# Lambda-Sensor-Driver.net
KiCad netlist of a schematic drawn in Altium Designer
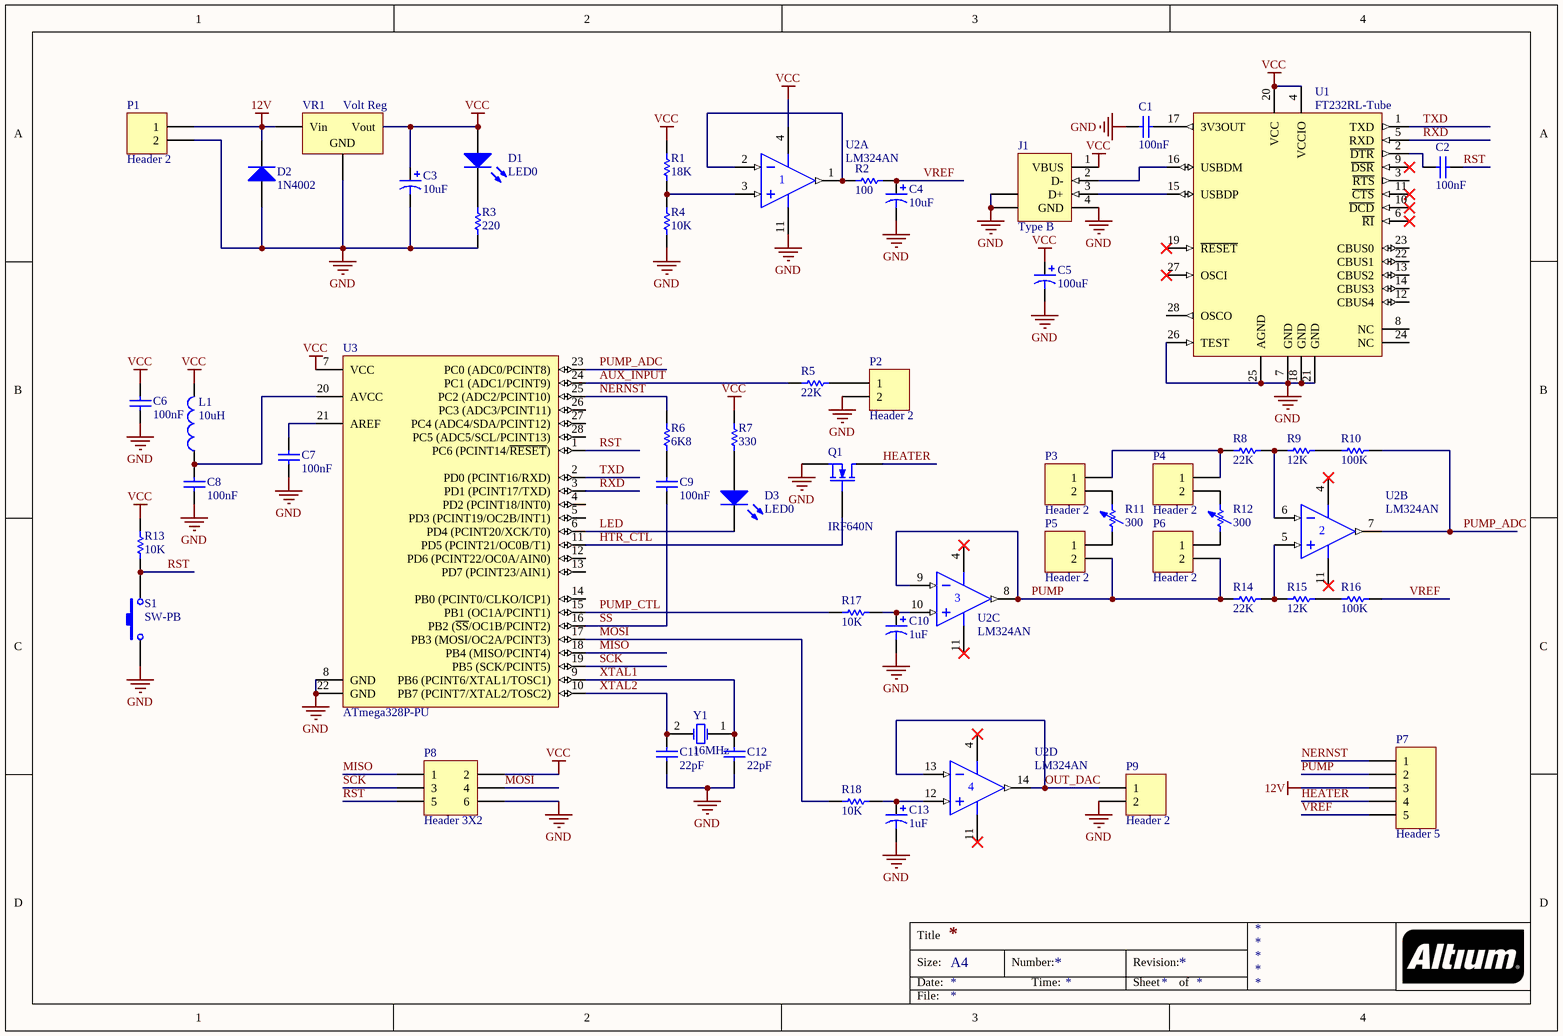
[diagram p0: Lambda-Sensor-Driver.SchDoc]

(export (version "E")
  (design (tool "Eeschema 10.0.6"))
  (components
    (comp (ref "C1")
      (value "100nF")
      (footprint "toko-Embedded:C0805")
      (description "Capacitor")
      (fields (field (name "PUBLISHER") "Altium Limited"))
      (libsource (lib "Miscellaneous Devices") (part "Cap"))
    )
    (comp (ref "C2")
      (value "100nF")
      (footprint "toko-Embedded:C0805")
      (description "Capacitor")
      (fields (field (name "PUBLISHER") "Altium Limited"))
      (libsource (lib "Miscellaneous Devices") (part "Cap"))
    )
    (comp (ref "C3")
      (value "10uF")
      (footprint "toko-Embedded:E2,5-5")
      (description "Polarized Capacitor (Radial)")
      (fields (field (name "PUBLISHER") "Altium Limited"))
      (libsource (lib "Miscellaneous Devices") (part "Cap Pol1"))
    )
    (comp (ref "C4")
      (value "10uF")
      (footprint "toko-Embedded:E2,5-5")
      (description "Polarized Capacitor (Radial)")
      (fields (field (name "PUBLISHER") "Altium Limited"))
      (libsource (lib "Miscellaneous Devices") (part "Cap Pol1"))
    )
    (comp (ref "C5")
      (value "100uF")
      (footprint "toko-Embedded:E2,5-5")
      (description "Polarized Capacitor (Radial)")
      (fields (field (name "PUBLISHER") "Altium Limited"))
      (libsource (lib "Miscellaneous Devices") (part "Cap Pol1"))
    )
    (comp (ref "C6")
      (value "100nF")
      (footprint "toko-Embedded:C025-024X044")
      (description "Capacitor")
      (fields (field (name "PUBLISHER") "Altium Limited"))
      (libsource (lib "Miscellaneous Devices") (part "Cap"))
    )
    (comp (ref "C7")
      (value "100nF")
      (footprint "toko-Embedded:C025-024X044")
      (description "Capacitor")
      (fields (field (name "PUBLISHER") "Altium Limited"))
      (libsource (lib "Miscellaneous Devices") (part "Cap"))
    )
    (comp (ref "C8")
      (value "100nF")
      (footprint "toko-Embedded:C025-024X044")
      (description "Capacitor")
      (fields (field (name "PUBLISHER") "Altium Limited"))
      (libsource (lib "Miscellaneous Devices") (part "Cap"))
    )
    (comp (ref "C9")
      (value "100nF")
      (footprint "toko-Embedded:C025-024X044")
      (description "Capacitor")
      (fields (field (name "PUBLISHER") "Altium Limited"))
      (libsource (lib "Miscellaneous Devices") (part "Cap"))
    )
    (comp (ref "C10")
      (value "1uF")
      (footprint "toko-Embedded:E2,5-5")
      (description "Polarized Capacitor (Radial)")
      (fields (field (name "PUBLISHER") "Altium Limited"))
      (libsource (lib "Miscellaneous Devices") (part "Cap Pol1"))
    )
    (comp (ref "C11")
      (value "22pF")
      (footprint "toko-Embedded:C025-024X044")
      (description "Capacitor")
      (fields (field (name "PUBLISHER") "Altium Limited"))
      (libsource (lib "Miscellaneous Devices") (part "Cap"))
    )
    (comp (ref "C12")
      (value "22pF")
      (footprint "toko-Embedded:C025-024X044")
      (description "Capacitor")
      (fields (field (name "PUBLISHER") "Altium Limited"))
      (libsource (lib "Miscellaneous Devices") (part "Cap"))
    )
    (comp (ref "C13")
      (value "1uF")
      (footprint "toko-Embedded:E2,5-5")
      (description "Polarized Capacitor (Radial)")
      (fields (field (name "PUBLISHER") "Altium Limited"))
      (libsource (lib "Miscellaneous Devices") (part "Cap Pol1"))
    )
    (comp (ref "D1")
      (value "LED0")
      (footprint "toko-Embedded:LED3MM")
      (description "Typical INFRARED GaAs LED")
      (fields (field (name "PUBLISHER") "Altium Limited"))
      (libsource (lib "Miscellaneous Devices") (part "LED0"))
    )
    (comp (ref "D2")
      (value "1N4002")
      (footprint "toko-Embedded:DO41-10")
      (description "Default Diode")
      (fields (field (name "PUBLISHER") "Altium Limited"))
      (libsource (lib "Miscellaneous Devices") (part "Diode"))
    )
    (comp (ref "D3")
      (value "LED0")
      (footprint "toko-Embedded:LED3MM")
      (description "Typical INFRARED GaAs LED")
      (fields (field (name "PUBLISHER") "Altium Limited"))
      (libsource (lib "Miscellaneous Devices") (part "LED0"))
    )
    (comp (ref "J1") (value "Type B") (footprint "USB-B-PTH") (libsource (lib "toko-Embedded") (part "USB")))
    (comp (ref "L1")
      (value "10uH")
      (footprint "toko-Embedded:0207/10")
      (description "Inductor")
      (fields (field (name "PUBLISHER") "Altium Limited"))
      (libsource (lib "Miscellaneous Devices") (part "Inductor"))
    )
    (comp (ref "P1")
      (value "Header 2")
      (footprint "toko-Embedded:W237-132")
      (description "Header, 2-Pin")
      (fields (field (name "PUBLISHER") "Altium Limited"))
      (libsource (lib "Miscellaneous Connectors") (part "Header 2"))
    )
    (comp (ref "P2")
      (value "Header 2")
      (footprint "toko-Embedded:W237-132")
      (description "Header, 2-Pin")
      (fields (field (name "PUBLISHER") "Altium Limited"))
      (libsource (lib "") (part "Header 2_1"))
    )
    (comp (ref "P3")
      (value "Header 2")
      (footprint "Miscellaneous Connectors:HDR1X2")
      (description "Header, 2-Pin")
      (fields (field (name "PUBLISHER") "Altium Limited"))
      (libsource (lib "Miscellaneous Connectors") (part "Header 2"))
    )
    (comp (ref "P4")
      (value "Header 2")
      (footprint "Miscellaneous Connectors:HDR1X2")
      (description "Header, 2-Pin")
      (fields (field (name "PUBLISHER") "Altium Limited"))
      (libsource (lib "Miscellaneous Connectors") (part "Header 2"))
    )
    (comp (ref "P5")
      (value "Header 2")
      (footprint "Miscellaneous Connectors:HDR1X2")
      (description "Header, 2-Pin")
      (fields (field (name "PUBLISHER") "Altium Limited"))
      (libsource (lib "Miscellaneous Connectors") (part "Header 2"))
    )
    (comp (ref "P6")
      (value "Header 2")
      (footprint "Miscellaneous Connectors:HDR1X2")
      (description "Header, 2-Pin")
      (fields (field (name "PUBLISHER") "Altium Limited"))
      (libsource (lib "Miscellaneous Connectors") (part "Header 2"))
    )
    (comp (ref "P7")
      (value "Header 5")
      (footprint "toko-Embedded:W237-6P")
      (description "Header, 5-Pin")
      (fields (field (name "PUBLISHER") "Altium Limited"))
      (libsource (lib "Miscellaneous Connectors") (part "Header 5"))
    )
    (comp (ref "P8")
      (value "Header 3X2")
      (footprint "HDR2X3")
      (description "Header, 3-Pin, Dual row")
      (fields (field (name "PUBLISHER") "Altium Limited"))
      (libsource (lib "Miscellaneous Connectors") (part "Header 3X2"))
    )
    (comp (ref "P9")
      (value "Header 2")
      (footprint "toko-Embedded:W237-132")
      (description "Header, 2-Pin")
      (fields (field (name "PUBLISHER") "Altium Limited"))
      (libsource (lib "") (part "Header 2_1"))
    )
    (comp (ref "Q1")
      (value "IRF640N")
      (footprint "toko-Embedded:TO220V")
      (description "N-Channel MOSFET")
      (fields (field (name "PUBLISHER") "Altium Limited"))
      (libsource (lib "Miscellaneous Devices") (part "MOSFET-N"))
    )
    (comp (ref "R1")
      (value "18K")
      (footprint "toko-Embedded:0207/10")
      (description "Resistor")
      (fields (field (name "PUBLISHER") "Altium Limited"))
      (libsource (lib "Miscellaneous Devices") (part "Res1"))
    )
    (comp (ref "R2")
      (value "100")
      (footprint "toko-Embedded:0207/10")
      (description "Resistor")
      (fields (field (name "PUBLISHER") "Altium Limited"))
      (libsource (lib "Miscellaneous Devices") (part "Res1"))
    )
    (comp (ref "R3")
      (value "220")
      (footprint "toko-Embedded:0207/10")
      (description "Resistor")
      (fields (field (name "PUBLISHER") "Altium Limited"))
      (libsource (lib "Miscellaneous Devices") (part "Res1"))
    )
    (comp (ref "R4")
      (value "10K")
      (footprint "toko-Embedded:0207/10")
      (description "Resistor")
      (fields (field (name "PUBLISHER") "Altium Limited"))
      (libsource (lib "Miscellaneous Devices") (part "Res1"))
    )
    (comp (ref "R5")
      (value "22K")
      (footprint "toko-Embedded:0207/10")
      (description "Resistor")
      (fields (field (name "PUBLISHER") "Altium Limited"))
      (libsource (lib "Miscellaneous Devices") (part "Res1"))
    )
    (comp (ref "R6")
      (value "6K8")
      (footprint "toko-Embedded:0207/10")
      (description "Resistor")
      (fields (field (name "PUBLISHER") "Altium Limited"))
      (libsource (lib "Miscellaneous Devices") (part "Res1"))
    )
    (comp (ref "R7")
      (value "330")
      (footprint "toko-Embedded:0207/10")
      (description "Resistor")
      (fields (field (name "PUBLISHER") "Altium Limited"))
      (libsource (lib "Miscellaneous Devices") (part "Res1"))
    )
    (comp (ref "R8")
      (value "22K")
      (footprint "toko-Embedded:0207/10")
      (description "Resistor")
      (fields (field (name "PUBLISHER") "Altium Limited"))
      (libsource (lib "Miscellaneous Devices") (part "Res1"))
    )
    (comp (ref "R9")
      (value "12K")
      (footprint "toko-Embedded:0207/10")
      (description "Resistor")
      (fields (field (name "PUBLISHER") "Altium Limited"))
      (libsource (lib "Miscellaneous Devices") (part "Res1"))
    )
    (comp (ref "R10")
      (value "100K")
      (footprint "toko-Embedded:0207/10")
      (description "Resistor")
      (fields (field (name "PUBLISHER") "Altium Limited"))
      (libsource (lib "Miscellaneous Devices") (part "Res1"))
    )
    (comp (ref "R11")
      (value "300")
      (footprint "toko-Embedded:CA6V")
      (description "Variable Resistor")
      (fields (field (name "PUBLISHER") "Altium Limited"))
      (libsource (lib "Miscellaneous Devices") (part "Res Adj1"))
    )
    (comp (ref "R12")
      (value "300")
      (footprint "toko-Embedded:CA6V")
      (description "Variable Resistor")
      (fields (field (name "PUBLISHER") "Altium Limited"))
      (libsource (lib "Miscellaneous Devices") (part "Res Adj1"))
    )
    (comp (ref "R13")
      (value "10K")
      (footprint "toko-Embedded:0207/10")
      (description "Resistor")
      (fields (field (name "PUBLISHER") "Altium Limited"))
      (libsource (lib "Miscellaneous Devices") (part "Res1"))
    )
    (comp (ref "R14")
      (value "22K")
      (footprint "toko-Embedded:0207/10")
      (description "Resistor")
      (fields (field (name "PUBLISHER") "Altium Limited"))
      (libsource (lib "Miscellaneous Devices") (part "Res1"))
    )
    (comp (ref "R15")
      (value "12K")
      (footprint "toko-Embedded:0207/10")
      (description "Resistor")
      (fields (field (name "PUBLISHER") "Altium Limited"))
      (libsource (lib "Miscellaneous Devices") (part "Res1"))
    )
    (comp (ref "R16")
      (value "100K")
      (footprint "toko-Embedded:0207/10")
      (description "Resistor")
      (fields (field (name "PUBLISHER") "Altium Limited"))
      (libsource (lib "Miscellaneous Devices") (part "Res1"))
    )
    (comp (ref "R17")
      (value "10K")
      (footprint "toko-Embedded:0207/10")
      (description "Resistor")
      (fields (field (name "PUBLISHER") "Altium Limited"))
      (libsource (lib "Miscellaneous Devices") (part "Res1"))
    )
    (comp (ref "R18")
      (value "10K")
      (footprint "toko-Embedded:0207/10")
      (description "Resistor")
      (fields (field (name "PUBLISHER") "Altium Limited"))
      (libsource (lib "Miscellaneous Devices") (part "Res1"))
    )
    (comp (ref "S1")
      (value "SW-PB")
      (footprint "toko-Embedded:TACTILE-PTH")
      (description "Switch")
      (fields (field (name "PUBLISHER") "Altium Limited"))
      (libsource (lib "Miscellaneous Devices") (part "SW-PB"))
    )
    (comp (ref "U1")
      (value "FT232RL-Tube")
      (footprint "SSOP-28_N")
      (description "USB UART Asynchronous Serial Data Transfer Chip, SSOP-28, Tube")
      (fields (field (name "PUBLISHER") "Altium Limited"))
      (libsource (lib "FTDI Communication UART") (part "FT232RL-Tube"))
    )
    (comp (ref "U2")
      (value "LM324AN")
      (footprint "646-06")
      (description "Quad Low-Power Operational Amplifier")
      (fields (field (name "PUBLISHER") "Altium Limited"))
      (libsource (lib "Motorola Amplifier Operational Amplifier") (part "LM324AN"))
    )
    (comp (ref "U3")
      (value "ATmega328P-PU")
      (footprint "28P3")
      (fields (field (name "PUBLISHER") "Altium Limited"))
      (libsource (lib "Atmel Microcontroller 8-Bit megaAVR") (part "ATmega328P-PU"))
    )
    (comp (ref "VR1")
      (value "Volt Reg")
      (footprint "toko-Embedded:TO220V")
      (description "Voltage Regulator")
      (fields (field (name "PUBLISHER") "Altium Limited"))
      (libsource (lib "Miscellaneous Devices") (part "Volt Reg"))
    )
    (comp (ref "Y1")
      (value "16MHz")
      (footprint "toko-Embedded:HC49US")
      (description "Crystal Oscillator")
      (fields (field (name "PUBLISHER") "Altium Limited"))
      (libsource (lib "Miscellaneous Devices") (part "XTAL"))
    )
  )
  (nets
    (net (code "1") (name "/AUX_INPUT") (class "Default")
      (node (ref "R5") (pin "2") (pinfunction "2_2") (pintype "passive"))
      (node (ref "U3") (pin "24") (pinfunction "PC1_(ADC1/PCINT9)_24") (pintype "bidirectional"))
    )
    (net (code "2") (name "/HEATER") (class "Default")
      (node (ref "P7") (pin "4") (pinfunction "4_4") (pintype "passive"))
      (node (ref "Q1") (pin "2") (pinfunction "D_2") (pintype "passive"))
    )
    (net (code "3") (name "/HTR_CTL") (class "Default")
      (node (ref "Q1") (pin "1") (pinfunction "G_1") (pintype "passive"))
      (node (ref "U3") (pin "11") (pinfunction "PD5_(PCINT21/OC0B/T1)_11") (pintype "bidirectional"))
    )
    (net (code "4") (name "/LED") (class "Default")
      (node (ref "D3") (pin "2") (pinfunction "K_2") (pintype "passive"))
      (node (ref "U3") (pin "6") (pinfunction "PD4_(PCINT20/XCK/T0)_6") (pintype "bidirectional"))
    )
    (net (code "5") (name "/MISO") (class "Default")
      (node (ref "P8") (pin "1") (pinfunction "1_1") (pintype "passive"))
      (node (ref "U3") (pin "18") (pinfunction "PB4_(MISO/PCINT4)_18") (pintype "bidirectional"))
    )
    (net (code "6") (name "/MOSI") (class "Default")
      (node (ref "P8") (pin "4") (pinfunction "4_4") (pintype "passive"))
      (node (ref "R18") (pin "1") (pinfunction "1_1") (pintype "passive"))
      (node (ref "U3") (pin "17") (pinfunction "PB3_(MOSI/OC2A/PCINT3)_17") (pintype "bidirectional"))
    )
    (net (code "7") (name "/NERNST") (class "Default")
      (node (ref "P7") (pin "1") (pinfunction "1_1") (pintype "passive"))
      (node (ref "R6") (pin "1") (pinfunction "1_1") (pintype "passive"))
      (node (ref "U3") (pin "25") (pinfunction "PC2_(ADC2/PCINT10)_25") (pintype "bidirectional"))
    )
    (net (code "8") (name "/OUT_DAC") (class "Default")
      (node (ref "P9") (pin "1") (pinfunction "1_1") (pintype "passive"))
      (node (ref "U2") (pin "13") (pinfunction "IN-_13") (pintype "input"))
      (node (ref "U2") (pin "14") (pinfunction "OUT_14") (pintype "output"))
    )
    (net (code "9") (name "/PUMP") (class "Default")
      (node (ref "P5") (pin "2") (pinfunction "2_2") (pintype "passive"))
      (node (ref "P6") (pin "2") (pinfunction "2_2") (pintype "passive"))
      (node (ref "P7") (pin "2") (pinfunction "2_2") (pintype "passive"))
      (node (ref "R14") (pin "2") (pinfunction "2_2") (pintype "passive"))
      (node (ref "U2") (pin "8") (pinfunction "OUT_8") (pintype "output"))
      (node (ref "U2") (pin "9") (pinfunction "IN-_9") (pintype "input"))
    )
    (net (code "10") (name "/PUMP_ADC") (class "Default")
      (node (ref "R10") (pin "1") (pinfunction "1_1") (pintype "passive"))
      (node (ref "U2") (pin "7") (pinfunction "OUT_7") (pintype "output"))
      (node (ref "U3") (pin "23") (pinfunction "PC0_(ADC0/PCINT8)_23") (pintype "bidirectional"))
    )
    (net (code "11") (name "/PUMP_CTL") (class "Default")
      (node (ref "R17") (pin "1") (pinfunction "1_1") (pintype "passive"))
      (node (ref "U3") (pin "15") (pinfunction "PB1_(OC1A/PCINT1)_15") (pintype "bidirectional"))
    )
    (net (code "12") (name "/RST") (class "Default")
      (node (ref "C2") (pin "1") (pinfunction "1_1") (pintype "passive"))
      (node (ref "P8") (pin "5") (pinfunction "5_5") (pintype "passive"))
      (node (ref "R13") (pin "2") (pinfunction "2_2") (pintype "passive"))
      (node (ref "S1") (pin "2") (pinfunction "2_2") (pintype "passive"))
      (node (ref "U3") (pin "1") (pinfunction "PC6_(PCINT14/~{RESET})_1") (pintype "bidirectional"))
    )
    (net (code "13") (name "/RXD") (class "Default")
      (node (ref "U1") (pin "5") (pinfunction "RXD_5") (pintype "input"))
      (node (ref "U3") (pin "3") (pinfunction "PD1_(PCINT17/TXD)_3") (pintype "bidirectional"))
    )
    (net (code "14") (name "/SCK") (class "Default")
      (node (ref "P8") (pin "3") (pinfunction "3_3") (pintype "passive"))
      (node (ref "U3") (pin "19") (pinfunction "PB5_(SCK/PCINT5)_19") (pintype "bidirectional"))
    )
    (net (code "15") (name "/SS") (class "Default")
      (node (ref "C9") (pin "1") (pinfunction "1_1") (pintype "passive"))
      (node (ref "U3") (pin "16") (pinfunction "PB2_(~{SS}/OC1B/PCINT2)_16") (pintype "bidirectional"))
    )
    (net (code "16") (name "/TXD") (class "Default")
      (node (ref "U1") (pin "1") (pinfunction "TXD_1") (pintype "output"))
      (node (ref "U3") (pin "2") (pinfunction "PD0_(PCINT16/RXD)_2") (pintype "bidirectional"))
    )
    (net (code "17") (name "/VREF") (class "Default")
      (node (ref "C4") (pin "1") (pinfunction "1_1") (pintype "passive"))
      (node (ref "P7") (pin "5") (pinfunction "5_5") (pintype "passive"))
      (node (ref "R16") (pin "1") (pinfunction "1_1") (pintype "passive"))
      (node (ref "R2") (pin "1") (pinfunction "1_1") (pintype "passive"))
    )
    (net (code "18") (name "/XTAL1") (class "Default")
      (node (ref "C12") (pin "2") (pinfunction "2_2") (pintype "passive"))
      (node (ref "U3") (pin "9") (pinfunction "PB6_(PCINT6/XTAL1/TOSC1)_9") (pintype "bidirectional"))
      (node (ref "Y1") (pin "1") (pinfunction "OSC1_1") (pintype "passive"))
    )
    (net (code "19") (name "/XTAL2") (class "Default")
      (node (ref "C11") (pin "2") (pinfunction "2_2") (pintype "passive"))
      (node (ref "U3") (pin "10") (pinfunction "PB7_(PCINT7/XTAL2/TOSC2)_10") (pintype "bidirectional"))
      (node (ref "Y1") (pin "2") (pinfunction "OSC2_2") (pintype "passive"))
    )
    (net (code "20") (name "12V") (class "Default")
      (node (ref "D2") (pin "2") (pinfunction "K_2") (pintype "passive"))
      (node (ref "P1") (pin "1") (pinfunction "1_1") (pintype "passive"))
      (node (ref "P7") (pin "3") (pinfunction "3_3") (pintype "passive"))
      (node (ref "VR1") (pin "1") (pinfunction "Vin_1") (pintype "passive"))
    )
    (net (code "21") (name "GND") (class "Default")
      (node (ref "C1") (pin "2") (pinfunction "2_2") (pintype "passive"))
      (node (ref "C10") (pin "2") (pinfunction "2_2") (pintype "passive"))
      (node (ref "C11") (pin "1") (pinfunction "1_1") (pintype "passive"))
      (node (ref "C12") (pin "1") (pinfunction "1_1") (pintype "passive"))
      (node (ref "C13") (pin "2") (pinfunction "2_2") (pintype "passive"))
      (node (ref "C3") (pin "2") (pinfunction "2_2") (pintype "passive"))
      (node (ref "C4") (pin "2") (pinfunction "2_2") (pintype "passive"))
      (node (ref "C5") (pin "2") (pinfunction "2_2") (pintype "passive"))
      (node (ref "C6") (pin "1") (pinfunction "1_1") (pintype "passive"))
      (node (ref "C7") (pin "1") (pinfunction "1_1") (pintype "passive"))
      (node (ref "C8") (pin "1") (pinfunction "1_1") (pintype "passive"))
      (node (ref "D2") (pin "1") (pinfunction "A_1") (pintype "passive"))
      (node (ref "J1") (pin "4") (pinfunction "GND_4") (pintype "power_in"))
      (node (ref "J1") (pin "5") (pinfunction "SHLD_5") (pintype "passive"))
      (node (ref "J1") (pin "6") (pinfunction "SHLD_6") (pintype "passive"))
      (node (ref "P1") (pin "2") (pinfunction "2_2") (pintype "passive"))
      (node (ref "P2") (pin "2") (pinfunction "2_2") (pintype "passive"))
      (node (ref "P8") (pin "6") (pinfunction "6_6") (pintype "passive"))
      (node (ref "P9") (pin "2") (pinfunction "2_2") (pintype "passive"))
      (node (ref "Q1") (pin "3") (pinfunction "S_3") (pintype "passive"))
      (node (ref "R3") (pin "1") (pinfunction "1_1") (pintype "passive"))
      (node (ref "R4") (pin "1") (pinfunction "1_1") (pintype "passive"))
      (node (ref "S1") (pin "1") (pinfunction "1_1") (pintype "passive"))
      (node (ref "U1") (pin "18") (pinfunction "GND_18") (pintype "power_in"))
      (node (ref "U1") (pin "21") (pinfunction "GND_21") (pintype "power_in"))
      (node (ref "U1") (pin "25") (pinfunction "AGND_25") (pintype "power_in"))
      (node (ref "U1") (pin "26") (pinfunction "TEST_26") (pintype "input"))
      (node (ref "U1") (pin "7") (pinfunction "GND_7") (pintype "power_in"))
      (node (ref "U2") (pin "11") (pinfunction "V-_11") (pintype "power_in"))
      (node (ref "U3") (pin "22") (pinfunction "GND_22") (pintype "power_in"))
      (node (ref "U3") (pin "8") (pinfunction "GND_8") (pintype "power_in"))
      (node (ref "VR1") (pin "2") (pinfunction "GND_2") (pintype "passive"))
    )
    (net (code "22") (name "Net-(C9-Pad2)") (class "Default")
      (node (ref "C9") (pin "2") (pinfunction "2_2") (pintype "passive"))
      (node (ref "R6") (pin "2") (pinfunction "2_2") (pintype "passive"))
    )
    (net (code "23") (name "Net-(D1-K)") (class "Default")
      (node (ref "D1") (pin "2") (pinfunction "K_2") (pintype "passive"))
      (node (ref "R3") (pin "2") (pinfunction "2_2") (pintype "passive"))
    )
    (net (code "24") (name "Net-(D3-A)") (class "Default")
      (node (ref "D3") (pin "1") (pinfunction "A_1") (pintype "passive"))
      (node (ref "R7") (pin "2") (pinfunction "2_2") (pintype "passive"))
    )
    (net (code "25") (name "Net-(J1-D+)") (class "Default")
      (node (ref "J1") (pin "3") (pinfunction "D+_3") (pintype "input"))
      (node (ref "U1") (pin "15") (pinfunction "USBDP_15") (pintype "bidirectional"))
    )
    (net (code "26") (name "Net-(J1-D-)") (class "Default")
      (node (ref "J1") (pin "2") (pinfunction "D-_2") (pintype "input"))
      (node (ref "U1") (pin "16") (pinfunction "USBDM_16") (pintype "bidirectional"))
    )
    (net (code "27") (name "Net-(P2-Pad1)") (class "Default")
      (node (ref "P2") (pin "1") (pinfunction "1_1") (pintype "passive"))
      (node (ref "R5") (pin "1") (pinfunction "1_1") (pintype "passive"))
    )
    (net (code "28") (name "Net-(P3-Pad1)") (class "Default")
      (node (ref "P3") (pin "1") (pinfunction "1_1") (pintype "passive"))
      (node (ref "P4") (pin "1") (pinfunction "1_1") (pintype "passive"))
      (node (ref "R8") (pin "2") (pinfunction "2_2") (pintype "passive"))
    )
    (net (code "29") (name "Net-(P3-Pad2)") (class "Default")
      (node (ref "P3") (pin "2") (pinfunction "2_2") (pintype "passive"))
      (node (ref "R11") (pin "2") (pinfunction "2_2") (pintype "passive"))
    )
    (net (code "30") (name "Net-(P4-Pad2)") (class "Default")
      (node (ref "P4") (pin "2") (pinfunction "2_2") (pintype "passive"))
      (node (ref "R12") (pin "2") (pinfunction "2_2") (pintype "passive"))
    )
    (net (code "31") (name "Net-(P5-Pad1)") (class "Default")
      (node (ref "P5") (pin "1") (pinfunction "1_1") (pintype "passive"))
      (node (ref "R11") (pin "1") (pinfunction "1_1") (pintype "passive"))
    )
    (net (code "32") (name "Net-(P6-Pad1)") (class "Default")
      (node (ref "P6") (pin "1") (pinfunction "1_1") (pintype "passive"))
      (node (ref "R12") (pin "1") (pinfunction "1_1") (pintype "passive"))
    )
    (net (code "33") (name "Net-(R10-Pad2)") (class "Default")
      (node (ref "R10") (pin "2") (pinfunction "2_2") (pintype "passive"))
      (node (ref "R9") (pin "1") (pinfunction "1_1") (pintype "passive"))
    )
    (net (code "34") (name "Net-(R15-Pad1)") (class "Default")
      (node (ref "R15") (pin "1") (pinfunction "1_1") (pintype "passive"))
      (node (ref "R16") (pin "2") (pinfunction "2_2") (pintype "passive"))
    )
    (net (code "35") (name "Net-(U1-3V3OUT)") (class "Default")
      (node (ref "C1") (pin "1") (pinfunction "1_1") (pintype "passive"))
      (node (ref "U1") (pin "17") (pinfunction "3V3OUT_17") (pintype "output"))
    )
    (net (code "36") (name "Net-(U1-~{DTR})") (class "Default")
      (node (ref "C2") (pin "2") (pinfunction "2_2") (pintype "passive"))
      (node (ref "U1") (pin "2") (pinfunction "~{DTR}_2") (pintype "output"))
    )
    (net (code "37") (name "Net-(U2A-IN+)") (class "Default")
      (node (ref "R1") (pin "1") (pinfunction "1_1") (pintype "passive"))
      (node (ref "R4") (pin "2") (pinfunction "2_2") (pintype "passive"))
      (node (ref "U2") (pin "3") (pinfunction "IN+_3") (pintype "input"))
    )
    (net (code "38") (name "Net-(U2A-IN-)") (class "Default")
      (node (ref "R2") (pin "2") (pinfunction "2_2") (pintype "passive"))
      (node (ref "U2") (pin "1") (pinfunction "OUT_1") (pintype "output"))
      (node (ref "U2") (pin "2") (pinfunction "IN-_2") (pintype "input"))
    )
    (net (code "39") (name "Net-(U2B-IN+)") (class "Default")
      (node (ref "R14") (pin "1") (pinfunction "1_1") (pintype "passive"))
      (node (ref "R15") (pin "2") (pinfunction "2_2") (pintype "passive"))
      (node (ref "U2") (pin "5") (pinfunction "IN+_5") (pintype "input"))
    )
    (net (code "40") (name "Net-(U2B-IN-)") (class "Default")
      (node (ref "R8") (pin "1") (pinfunction "1_1") (pintype "passive"))
      (node (ref "R9") (pin "2") (pinfunction "2_2") (pintype "passive"))
      (node (ref "U2") (pin "6") (pinfunction "IN-_6") (pintype "input"))
    )
    (net (code "41") (name "Net-(U2C-IN+)") (class "Default")
      (node (ref "C10") (pin "1") (pinfunction "1_1") (pintype "passive"))
      (node (ref "R17") (pin "2") (pinfunction "2_2") (pintype "passive"))
      (node (ref "U2") (pin "10") (pinfunction "IN+_10") (pintype "input"))
    )
    (net (code "42") (name "Net-(U2D-IN+)") (class "Default")
      (node (ref "C13") (pin "1") (pinfunction "1_1") (pintype "passive"))
      (node (ref "R18") (pin "2") (pinfunction "2_2") (pintype "passive"))
      (node (ref "U2") (pin "12") (pinfunction "IN+_12") (pintype "input"))
    )
    (net (code "43") (name "Net-(U3-AREF)") (class "Default")
      (node (ref "C7") (pin "2") (pinfunction "2_2") (pintype "passive"))
      (node (ref "U3") (pin "21") (pinfunction "AREF_21") (pintype "power_in"))
    )
    (net (code "44") (name "Net-(U3-AVCC)") (class "Default")
      (node (ref "C8") (pin "2") (pinfunction "2_2") (pintype "passive"))
      (node (ref "L1") (pin "1") (pinfunction "1_1") (pintype "passive"))
      (node (ref "U3") (pin "20") (pinfunction "AVCC_20") (pintype "power_in"))
    )
    (net (code "45") (name "VCC") (class "Default")
      (node (ref "C3") (pin "1") (pinfunction "1_1") (pintype "passive"))
      (node (ref "C5") (pin "1") (pinfunction "1_1") (pintype "passive"))
      (node (ref "C6") (pin "2") (pinfunction "2_2") (pintype "passive"))
      (node (ref "D1") (pin "1") (pinfunction "A_1") (pintype "passive"))
      (node (ref "J1") (pin "1") (pinfunction "VBUS_1") (pintype "power_in"))
      (node (ref "L1") (pin "2") (pinfunction "2_2") (pintype "passive"))
      (node (ref "P8") (pin "2") (pinfunction "2_2") (pintype "passive"))
      (node (ref "R1") (pin "2") (pinfunction "2_2") (pintype "passive"))
      (node (ref "R13") (pin "1") (pinfunction "1_1") (pintype "passive"))
      (node (ref "R7") (pin "1") (pinfunction "1_1") (pintype "passive"))
      (node (ref "U1") (pin "20") (pinfunction "VCC_20") (pintype "power_in"))
      (node (ref "U1") (pin "4") (pinfunction "VCCIO_4") (pintype "power_in"))
      (node (ref "U2") (pin "4") (pinfunction "V+_4") (pintype "power_in"))
      (node (ref "U3") (pin "7") (pinfunction "VCC_7") (pintype "power_in"))
      (node (ref "VR1") (pin "3") (pinfunction "Vout_3") (pintype "passive"))
    )
    (net (code "46") (name "unconnected-(U1-CBUS0-Pad23)") (class "Default")
      (node (ref "U1") (pin "23") (pinfunction "CBUS0_23") (pintype "bidirectional"))
    )
    (net (code "47") (name "unconnected-(U1-CBUS1-Pad22)") (class "Default")
      (node (ref "U1") (pin "22") (pinfunction "CBUS1_22") (pintype "bidirectional"))
    )
    (net (code "48") (name "unconnected-(U1-CBUS2-Pad13)") (class "Default")
      (node (ref "U1") (pin "13") (pinfunction "CBUS2_13") (pintype "bidirectional"))
    )
    (net (code "49") (name "unconnected-(U1-CBUS3-Pad14)") (class "Default")
      (node (ref "U1") (pin "14") (pinfunction "CBUS3_14") (pintype "bidirectional"))
    )
    (net (code "50") (name "unconnected-(U1-CBUS4-Pad12)") (class "Default")
      (node (ref "U1") (pin "12") (pinfunction "CBUS4_12") (pintype "bidirectional"))
    )
    (net (code "51") (name "unconnected-(U1-NC-Pad8)") (class "Default")
      (node (ref "U1") (pin "8") (pinfunction "NC_8") (pintype "passive"))
    )
    (net (code "52") (name "unconnected-(U1-NC-Pad24)") (class "Default")
      (node (ref "U1") (pin "24") (pinfunction "NC_24") (pintype "passive"))
    )
    (net (code "53") (name "unconnected-(U1-OSCI-Pad27)") (class "Default")
      (node (ref "U1") (pin "27") (pinfunction "OSCI_27") (pintype "input+no_connect"))
    )
    (net (code "54") (name "unconnected-(U1-OSCO-Pad28)") (class "Default")
      (node (ref "U1") (pin "28") (pinfunction "OSCO_28") (pintype "output"))
    )
    (net (code "55") (name "unconnected-(U1-~{CTS}-Pad11)") (class "Default")
      (node (ref "U1") (pin "11") (pinfunction "~{CTS}_11") (pintype "input+no_connect"))
    )
    (net (code "56") (name "unconnected-(U1-~{DCD}-Pad10)") (class "Default")
      (node (ref "U1") (pin "10") (pinfunction "~{DCD}_10") (pintype "input+no_connect"))
    )
    (net (code "57") (name "unconnected-(U1-~{DSR}-Pad9)") (class "Default")
      (node (ref "U1") (pin "9") (pinfunction "~{DSR}_9") (pintype "input+no_connect"))
    )
    (net (code "58") (name "unconnected-(U1-~{RESET}-Pad19)") (class "Default")
      (node (ref "U1") (pin "19") (pinfunction "~{RESET}_19") (pintype "input+no_connect"))
    )
    (net (code "59") (name "unconnected-(U1-~{RI}-Pad6)") (class "Default")
      (node (ref "U1") (pin "6") (pinfunction "~{RI}_6") (pintype "input+no_connect"))
    )
    (net (code "60") (name "unconnected-(U1-~{RTS}-Pad3)") (class "Default")
      (node (ref "U1") (pin "3") (pinfunction "~{RTS}_3") (pintype "output"))
    )
    (net (code "61") (name "unconnected-(U2B-V+-Pad4)") (class "Default")
      (node (ref "U2") (pin "4") (pinfunction "V+_4") (pintype "power_in+no_connect"))
    )
    (net (code "62") (name "unconnected-(U2B-V--Pad11)") (class "Default")
      (node (ref "U2") (pin "11") (pinfunction "V-_11") (pintype "power_in+no_connect"))
    )
    (net (code "63") (name "unconnected-(U2C-V+-Pad4)") (class "Default")
      (node (ref "U2") (pin "4") (pinfunction "V+_4") (pintype "power_in+no_connect"))
    )
    (net (code "64") (name "unconnected-(U2C-V--Pad11)") (class "Default")
      (node (ref "U2") (pin "11") (pinfunction "V-_11") (pintype "power_in+no_connect"))
    )
    (net (code "65") (name "unconnected-(U2D-V+-Pad4)") (class "Default")
      (node (ref "U2") (pin "4") (pinfunction "V+_4") (pintype "power_in+no_connect"))
    )
    (net (code "66") (name "unconnected-(U2D-V--Pad11)") (class "Default")
      (node (ref "U2") (pin "11") (pinfunction "V-_11") (pintype "power_in+no_connect"))
    )
    (net (code "67") (name "unconnected-(U3-PB0_(PCINT0{slash}CLKO{slash}ICP1)-Pad14)") (class "Default")
      (node (ref "U3") (pin "14") (pinfunction "PB0_(PCINT0/CLKO/ICP1)_14") (pintype "bidirectional"))
    )
    (net (code "68") (name "unconnected-(U3-PC3_(ADC3{slash}PCINT11)-Pad26)") (class "Default")
      (node (ref "U3") (pin "26") (pinfunction "PC3_(ADC3/PCINT11)_26") (pintype "bidirectional"))
    )
    (net (code "69") (name "unconnected-(U3-PC4_(ADC4{slash}SDA{slash}PCINT12)-Pad27)") (class "Default")
      (node (ref "U3") (pin "27") (pinfunction "PC4_(ADC4/SDA/PCINT12)_27") (pintype "bidirectional"))
    )
    (net (code "70") (name "unconnected-(U3-PC5_(ADC5{slash}SCL{slash}PCINT13)-Pad28)") (class "Default")
      (node (ref "U3") (pin "28") (pinfunction "PC5_(ADC5/SCL/PCINT13)_28") (pintype "bidirectional"))
    )
    (net (code "71") (name "unconnected-(U3-PD2_(PCINT18{slash}INT0)-Pad4)") (class "Default")
      (node (ref "U3") (pin "4") (pinfunction "PD2_(PCINT18/INT0)_4") (pintype "bidirectional"))
    )
    (net (code "72") (name "unconnected-(U3-PD3_(PCINT19{slash}OC2B{slash}INT1)-Pad5)") (class "Default")
      (node (ref "U3") (pin "5") (pinfunction "PD3_(PCINT19/OC2B/INT1)_5") (pintype "bidirectional"))
    )
    (net (code "73") (name "unconnected-(U3-PD6_(PCINT22{slash}OC0A{slash}AIN0)-Pad12)") (class "Default")
      (node (ref "U3") (pin "12") (pinfunction "PD6_(PCINT22/OC0A/AIN0)_12") (pintype "bidirectional"))
    )
    (net (code "74") (name "unconnected-(U3-PD7_(PCINT23{slash}AIN1)-Pad13)") (class "Default")
      (node (ref "U3") (pin "13") (pinfunction "PD7_(PCINT23/AIN1)_13") (pintype "bidirectional"))
    )
  )
)
